# controller.net
KiCad netlist of a schematic drawn in EAGLE
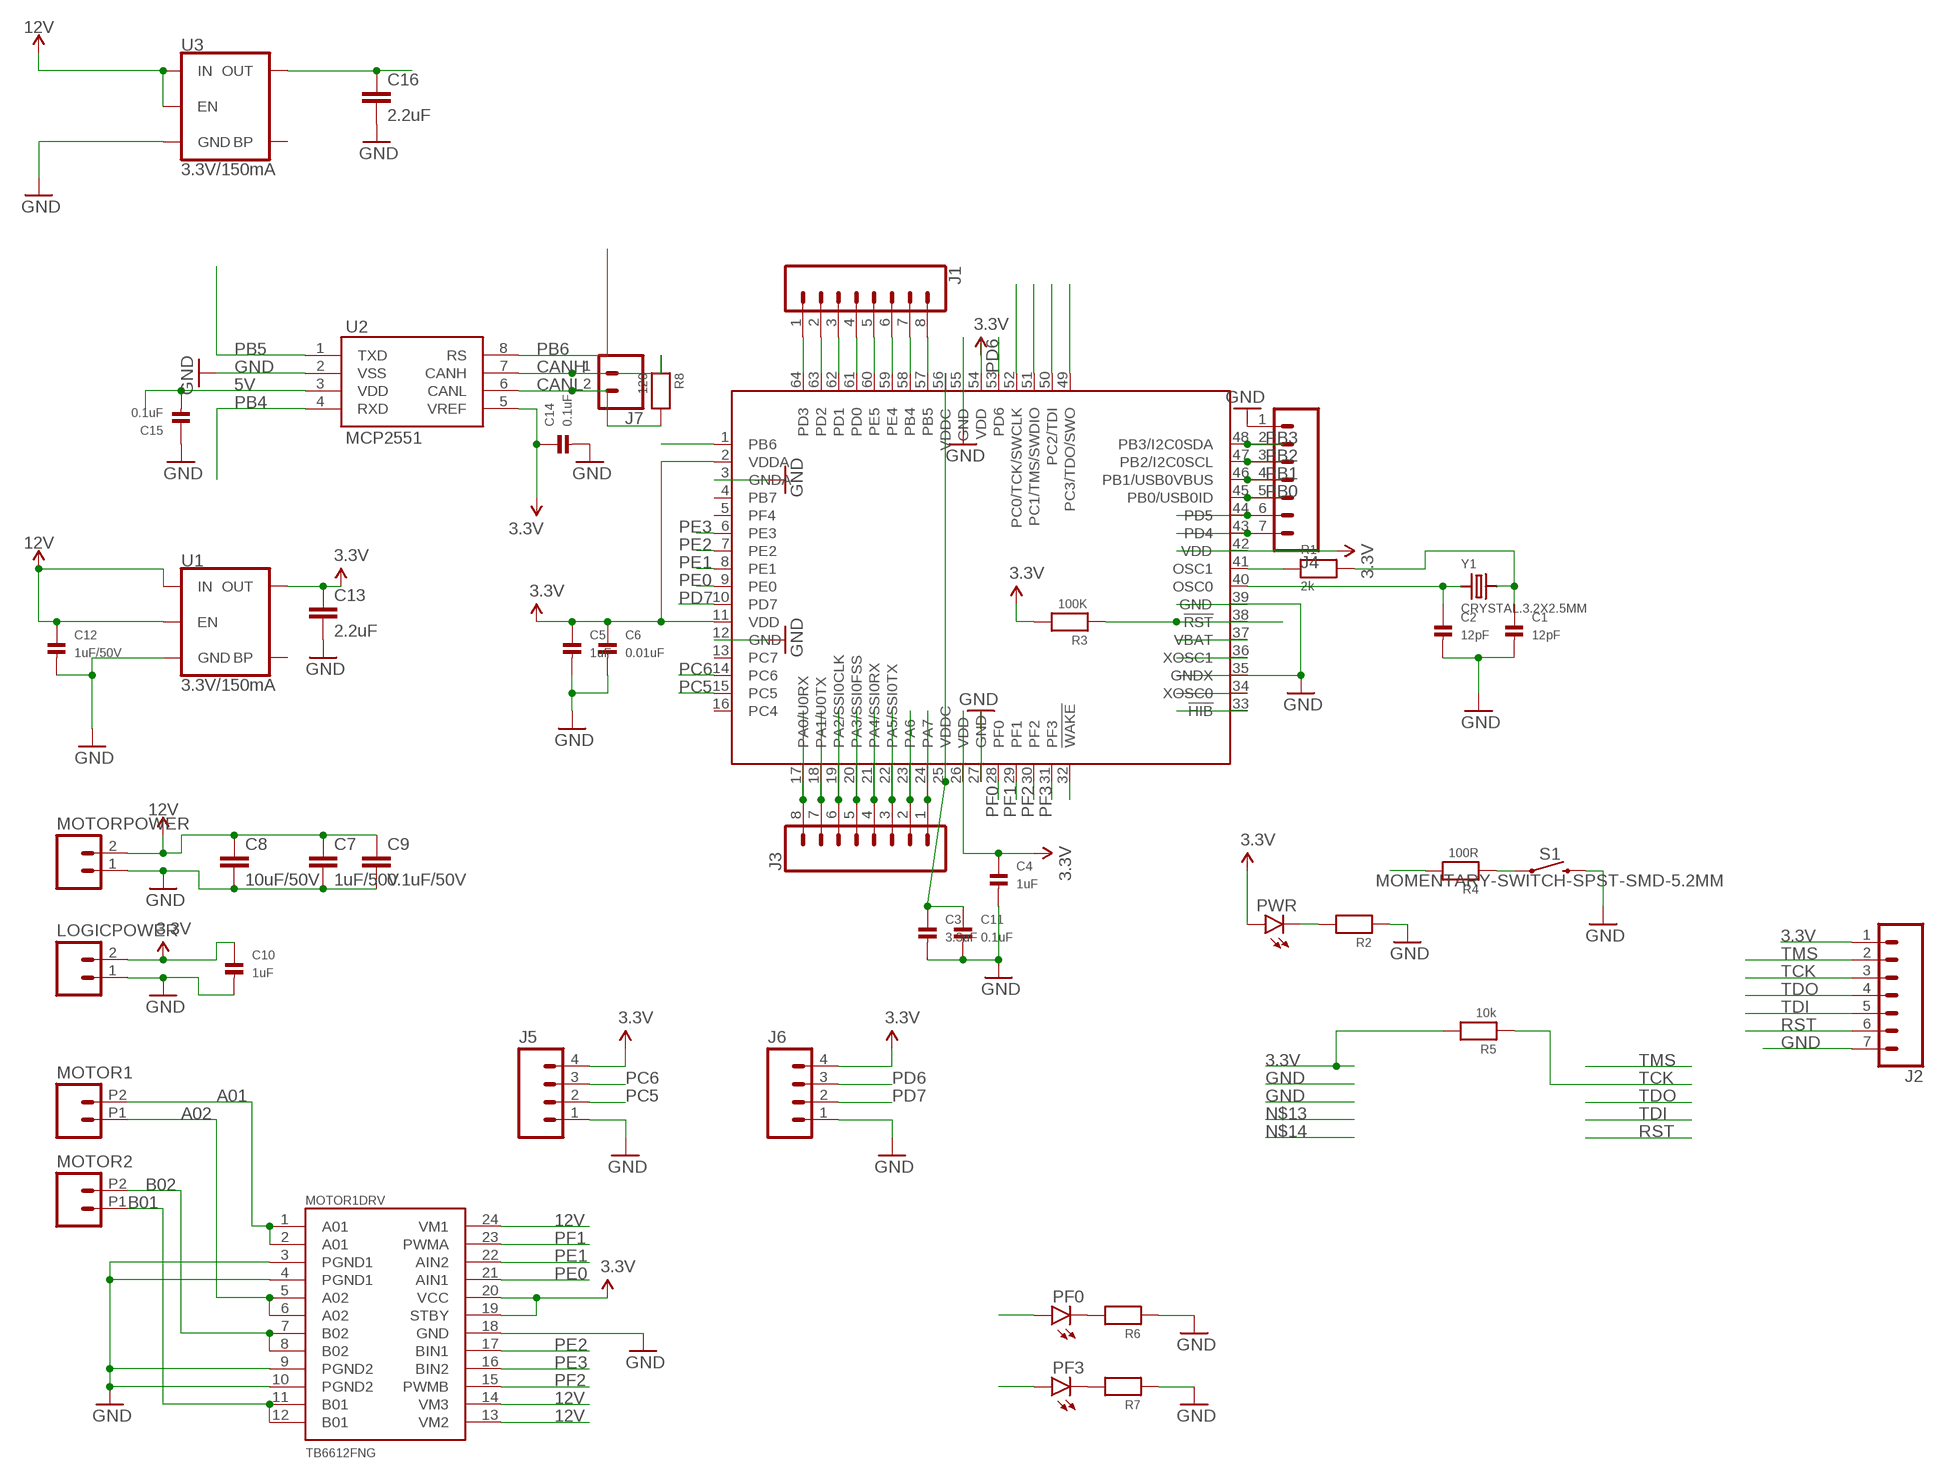
[diagram p0: schematic, sheet 1]

(export (version "E")
  (design (tool "Eeschema 10.0.6"))
  (components
    (comp (ref "C1")
      (value "12pF")
      (footprint "eagle-import:_0603MP")
      (libsource (lib "eagle-import") (part "CAP_CERAMIC_0603MP"))
    )
    (comp (ref "C2")
      (value "12pF")
      (footprint "eagle-import:_0603MP")
      (libsource (lib "eagle-import") (part "CAP_CERAMIC_0603MP"))
    )
    (comp (ref "C3")
      (value "3.3uF")
      (footprint "eagle-import:_0603MP")
      (libsource (lib "eagle-import") (part "CAP_CERAMIC_0603MP"))
    )
    (comp (ref "C4")
      (value "1uF")
      (footprint "eagle-import:_0603MP")
      (libsource (lib "eagle-import") (part "CAP_CERAMIC_0603MP"))
    )
    (comp (ref "C5")
      (value "1uF")
      (footprint "eagle-import:_0603MP")
      (libsource (lib "eagle-import") (part "CAP_CERAMIC_0603MP"))
    )
    (comp (ref "C6")
      (value "0.01uF")
      (footprint "eagle-import:_0603MP")
      (libsource (lib "eagle-import") (part "CAP_CERAMIC_0603MP"))
    )
    (comp (ref "C7")
      (value "1uF/50V")
      (footprint "eagle-import:0603-CAP")
      (libsource (lib "eagle-import") (part "0.1UF-25V(+80/-20%)(0603)"))
    )
    (comp (ref "C8")
      (value "10uF/50V")
      (footprint "eagle-import:0805-CAP")
      (libsource (lib "eagle-import") (part "1.0UF-25V-+80/-20(0805){dblquote}"))
    )
    (comp (ref "C9")
      (value "0.1uF/50V")
      (footprint "eagle-import:0603-CAP")
      (libsource (lib "eagle-import") (part "0.1UF-25V(+80/-20%)(0603)"))
    )
    (comp (ref "C10")
      (value "1uF")
      (footprint "eagle-import:_0603MP")
      (libsource (lib "eagle-import") (part "CAP_CERAMIC_0603MP"))
    )
    (comp (ref "C11")
      (value "0.1uF")
      (footprint "eagle-import:_0603MP")
      (libsource (lib "eagle-import") (part "CAP_CERAMIC_0603MP"))
    )
    (comp (ref "C12")
      (value "1uF/50V")
      (footprint "eagle-import:_0603MP")
      (libsource (lib "eagle-import") (part "CAP_CERAMIC_0603MP"))
    )
    (comp (ref "C13")
      (value "2.2uF")
      (footprint "eagle-import:0805")
      (libsource (lib "eagle-import") (part "2.2UF-0805-25V-(+80/-20%)"))
    )
    (comp (ref "C14")
      (value "0.1uF")
      (footprint "eagle-import:_0603MP")
      (libsource (lib "eagle-import") (part "CAP_CERAMIC_0603MP"))
    )
    (comp (ref "C15")
      (value "0.1uF")
      (footprint "eagle-import:_0603MP")
      (libsource (lib "eagle-import") (part "CAP_CERAMIC_0603MP"))
    )
    (comp (ref "C16")
      (value "2.2uF")
      (footprint "eagle-import:0805")
      (libsource (lib "eagle-import") (part "2.2UF-0805-25V-(+80/-20%)"))
    )
    (comp (ref "IC1")
      (value "TM4C123[7,G]XXPM")
      (footprint "eagle-import:PM_S-PQFP-G64")
      (libsource (lib "eagle-import") (part "TM4C123[7,G]XXPM"))
    )
    (comp (ref "J1")
      (value "CONN_08\"")
      (footprint "eagle-import:1X08@1")
      (libsource (lib "eagle-import") (part "CONN_08{dblquote}"))
    )
    (comp (ref "J2")
      (value "CONN_07")
      (footprint "eagle-import:1X07@1")
      (libsource (lib "eagle-import") (part "CONN_07"))
    )
    (comp (ref "J3")
      (value "CONN_08\"")
      (footprint "eagle-import:1X08@1")
      (libsource (lib "eagle-import") (part "CONN_08{dblquote}"))
    )
    (comp (ref "J4")
      (value "M07")
      (footprint "eagle-import:1X07")
      (libsource (lib "eagle-import") (part "M07"))
    )
    (comp (ref "J5")
      (value "M04PTH")
      (footprint "eagle-import:1X04")
      (libsource (lib "eagle-import") (part "M04PTH"))
    )
    (comp (ref "J6")
      (value "M04PTH")
      (footprint "eagle-import:1X04")
      (libsource (lib "eagle-import") (part "M04PTH"))
    )
    (comp (ref "J7")
      (value "CONN_02")
      (footprint "eagle-import:1X02")
      (libsource (lib "eagle-import") (part "CONN_02"))
    )
    (comp (ref "LOGICPOWER")
      (value "M02PTH")
      (footprint "eagle-import:1X02@1")
      (libsource (lib "eagle-import") (part "M02PTH"))
    )
    (comp (ref "MOTOR1")
      (value "M022.54MM_SCREWTERM")
      (footprint "eagle-import:1X02_2.54_SCREWTERM@1")
      (libsource (lib "eagle-import") (part "M022.54MM_SCREWTERM"))
    )
    (comp (ref "MOTOR1DRV")
      (value "TB6612FNG")
      (footprint "eagle-import:SSOP24")
      (libsource (lib "eagle-import") (part "TB6612FNG"))
    )
    (comp (ref "MOTOR2")
      (value "M022.54MM_SCREWTERM")
      (footprint "eagle-import:1X02_2.54_SCREWTERM@1")
      (libsource (lib "eagle-import") (part "M022.54MM_SCREWTERM"))
    )
    (comp (ref "MOTORPOWER")
      (value "M02PTH")
      (footprint "eagle-import:1X02@1")
      (libsource (lib "eagle-import") (part "M02PTH"))
    )
    (comp (ref "PF0")
      (value "LED0603")
      (footprint "eagle-import:LED-0603")
      (libsource (lib "eagle-import") (part "LED0603"))
    )
    (comp (ref "PF3")
      (value "LED0603")
      (footprint "eagle-import:LED-0603")
      (libsource (lib "eagle-import") (part "LED0603"))
    )
    (comp (ref "PWR")
      (value "LED0603")
      (footprint "eagle-import:LED-0603")
      (libsource (lib "eagle-import") (part "LED0603"))
    )
    (comp (ref "R1")
      (value "2k")
      (footprint "eagle-import:_0603MP")
      (libsource (lib "eagle-import") (part "RESISTOR_0603MP"))
    )
    (comp (ref "R2")
      (value "RESISTOR_0603MP")
      (footprint "eagle-import:_0603MP")
      (libsource (lib "eagle-import") (part "RESISTOR_0603MP"))
    )
    (comp (ref "R3")
      (value "100K")
      (footprint "eagle-import:_0603MP")
      (libsource (lib "eagle-import") (part "RESISTOR_0603MP"))
    )
    (comp (ref "R4")
      (value "100R")
      (footprint "eagle-import:_0603MP")
      (libsource (lib "eagle-import") (part "RESISTOR_0603MP"))
    )
    (comp (ref "R5")
      (value "10k")
      (footprint "eagle-import:_0603MP")
      (libsource (lib "eagle-import") (part "RESISTOR_0603MP"))
    )
    (comp (ref "R6")
      (value "RESISTOR_0603MP")
      (footprint "eagle-import:_0603MP")
      (libsource (lib "eagle-import") (part "RESISTOR_0603MP"))
    )
    (comp (ref "R7")
      (value "RESISTOR_0603MP")
      (footprint "eagle-import:_0603MP")
      (libsource (lib "eagle-import") (part "RESISTOR_0603MP"))
    )
    (comp (ref "R8")
      (value "120")
      (footprint "eagle-import:_0603MP")
      (libsource (lib "eagle-import") (part "RESISTOR_0603MP"))
    )
    (comp (ref "S1")
      (value "MOMENTARY-SWITCH-SPST-SMD-5.2MM")
      (footprint "eagle-import:TACTILE_SWITCH_SMD_5.2MM")
      (libsource (lib "eagle-import") (part "MOMENTARY-SWITCH-SPST-SMD-5.2MM"))
    )
    (comp (ref "U1")
      (value "3.3V/150mA")
      (footprint "eagle-import:SOT23-5")
      (libsource (lib "eagle-import") (part "V_REG_MIC52053.3V"))
    )
    (comp (ref "U2")
      (value "MCP2551")
      (footprint "eagle-import:SO08")
      (libsource (lib "eagle-import") (part "MCP2551"))
    )
    (comp (ref "U3")
      (value "3.3V/150mA")
      (footprint "eagle-import:SOT23-5")
      (libsource (lib "eagle-import") (part "V_REG_MIC52053.3V"))
    )
    (comp (ref "Y1")
      (value "CRYSTAL.3.2X2.5MM")
      (footprint "eagle-import:3.2X2.5MM")
      (libsource (lib "eagle-import") (part "CRYSTAL.3.2X2.5MM"))
    )
  )
  (nets
    (net (code "1") (name "/5V") (class "Default")
      (node (ref "C15") (pin "2") (pinfunction "P$2_2") (pintype "passive"))
      (node (ref "C16") (pin "1") (pinfunction "1_1") (pintype "passive"))
      (node (ref "U2") (pin "3") (pinfunction "VDD_3") (pintype "bidirectional"))
      (node (ref "U3") (pin "5") (pinfunction "OUT_5") (pintype "passive"))
    )
    (net (code "2") (name "/A01") (class "Default")
      (node (ref "MOTOR1") (pin "P2") (pinfunction "2_P2") (pintype "passive"))
      (node (ref "MOTOR1DRV") (pin "1") (pinfunction "A01_1") (pintype "bidirectional"))
      (node (ref "MOTOR1DRV") (pin "2") (pinfunction "A01_2") (pintype "bidirectional"))
    )
    (net (code "3") (name "/A02") (class "Default")
      (node (ref "MOTOR1") (pin "P1") (pinfunction "1_P1") (pintype "passive"))
      (node (ref "MOTOR1DRV") (pin "5") (pinfunction "A02_5") (pintype "bidirectional"))
      (node (ref "MOTOR1DRV") (pin "6") (pinfunction "A02_6") (pintype "bidirectional"))
    )
    (net (code "4") (name "/B01") (class "Default")
      (node (ref "MOTOR1DRV") (pin "11") (pinfunction "B01_11") (pintype "bidirectional"))
      (node (ref "MOTOR1DRV") (pin "12") (pinfunction "B01_12") (pintype "bidirectional"))
      (node (ref "MOTOR2") (pin "P1") (pinfunction "1_P1") (pintype "passive"))
    )
    (net (code "5") (name "/B02") (class "Default")
      (node (ref "MOTOR1DRV") (pin "7") (pinfunction "B02_7") (pintype "bidirectional"))
      (node (ref "MOTOR1DRV") (pin "8") (pinfunction "B02_8") (pintype "bidirectional"))
      (node (ref "MOTOR2") (pin "P2") (pinfunction "2_P2") (pintype "passive"))
    )
    (net (code "6") (name "/CANH") (class "Default")
      (node (ref "J7") (pin "1") (pinfunction "1_1") (pintype "passive"))
      (node (ref "R8") (pin "1") (pinfunction "1_1") (pintype "passive"))
      (node (ref "U2") (pin "7") (pinfunction "CANH_7") (pintype "bidirectional"))
    )
    (net (code "7") (name "/CANL") (class "Default")
      (node (ref "J7") (pin "2") (pinfunction "2_2") (pintype "passive"))
      (node (ref "R8") (pin "2") (pinfunction "2_2") (pintype "passive"))
      (node (ref "U2") (pin "6") (pinfunction "CANL_6") (pintype "bidirectional"))
    )
    (net (code "10") (name "/PB0") (class "Default")
      (node (ref "IC1") (pin "45") (pinfunction "PB0/USB0ID_45") (pintype "bidirectional"))
      (node (ref "J4") (pin "5") (pinfunction "5_5") (pintype "passive"))
    )
    (net (code "11") (name "/PB1") (class "Default")
      (node (ref "IC1") (pin "46") (pinfunction "PB1/USB0VBUS_46") (pintype "bidirectional"))
      (node (ref "J4") (pin "4") (pinfunction "4_4") (pintype "passive"))
    )
    (net (code "12") (name "/PB2") (class "Default")
      (node (ref "IC1") (pin "47") (pinfunction "PB2/I2C0SCL_47") (pintype "bidirectional"))
      (node (ref "J4") (pin "3") (pinfunction "3_3") (pintype "passive"))
    )
    (net (code "13") (name "/PB3") (class "Default")
      (node (ref "IC1") (pin "48") (pinfunction "PB3/I2C0SDA_48") (pintype "bidirectional"))
      (node (ref "J4") (pin "2") (pinfunction "2_2") (pintype "passive"))
    )
    (net (code "14") (name "/PB4") (class "Default")
      (node (ref "IC1") (pin "58") (pinfunction "PB4_58") (pintype "bidirectional"))
      (node (ref "J1") (pin "7") (pinfunction "7_7") (pintype "passive"))
      (node (ref "U2") (pin "4") (pinfunction "RXD_4") (pintype "bidirectional"))
    )
    (net (code "15") (name "/PB5") (class "Default")
      (node (ref "IC1") (pin "57") (pinfunction "PB5_57") (pintype "bidirectional"))
      (node (ref "J1") (pin "8") (pinfunction "8_8") (pintype "passive"))
      (node (ref "U2") (pin "1") (pinfunction "TXD_1") (pintype "bidirectional"))
    )
    (net (code "16") (name "/PB6") (class "Default")
      (node (ref "IC1") (pin "1") (pinfunction "PB6_1") (pintype "bidirectional"))
      (node (ref "U2") (pin "8") (pinfunction "RS_8") (pintype "bidirectional"))
    )
    (net (code "17") (name "/PC5") (class "Default")
      (node (ref "IC1") (pin "15") (pinfunction "PC5_15") (pintype "bidirectional"))
      (node (ref "J5") (pin "2") (pinfunction "2_2") (pintype "passive"))
    )
    (net (code "18") (name "/PC6") (class "Default")
      (node (ref "IC1") (pin "14") (pinfunction "PC6_14") (pintype "bidirectional"))
      (node (ref "J5") (pin "3") (pinfunction "3_3") (pintype "passive"))
    )
    (net (code "19") (name "/PD6") (class "Default")
      (node (ref "IC1") (pin "53") (pinfunction "PD6_53") (pintype "bidirectional"))
      (node (ref "J6") (pin "3") (pinfunction "3_3") (pintype "passive"))
    )
    (net (code "20") (name "/PD7") (class "Default")
      (node (ref "IC1") (pin "10") (pinfunction "PD7_10") (pintype "bidirectional"))
      (node (ref "J6") (pin "2") (pinfunction "2_2") (pintype "passive"))
    )
    (net (code "21") (name "/PE0") (class "Default")
      (node (ref "IC1") (pin "9") (pinfunction "PE0_9") (pintype "bidirectional"))
      (node (ref "MOTOR1DRV") (pin "21") (pinfunction "AIN1_21") (pintype "bidirectional"))
    )
    (net (code "22") (name "/PE1") (class "Default")
      (node (ref "IC1") (pin "8") (pinfunction "PE1_8") (pintype "bidirectional"))
      (node (ref "MOTOR1DRV") (pin "22") (pinfunction "AIN2_22") (pintype "bidirectional"))
    )
    (net (code "23") (name "/PE2") (class "Default")
      (node (ref "IC1") (pin "7") (pinfunction "PE2_7") (pintype "bidirectional"))
      (node (ref "MOTOR1DRV") (pin "17") (pinfunction "BIN1_17") (pintype "bidirectional"))
    )
    (net (code "24") (name "/PE3") (class "Default")
      (node (ref "IC1") (pin "6") (pinfunction "PE3_6") (pintype "bidirectional"))
      (node (ref "MOTOR1DRV") (pin "16") (pinfunction "BIN2_16") (pintype "bidirectional"))
    )
    (net (code "25") (name "/PF0") (class "Default")
      (node (ref "IC1") (pin "28") (pinfunction "PF0_28") (pintype "bidirectional"))
      (node (ref "PF0") (pin "A") (pinfunction "A_A") (pintype "passive"))
    )
    (net (code "26") (name "/PF1") (class "Default")
      (node (ref "IC1") (pin "29") (pinfunction "PF1_29") (pintype "bidirectional"))
      (node (ref "MOTOR1DRV") (pin "23") (pinfunction "PWMA_23") (pintype "bidirectional"))
    )
    (net (code "27") (name "/PF2") (class "Default")
      (node (ref "IC1") (pin "30") (pinfunction "PF2_30") (pintype "bidirectional"))
      (node (ref "MOTOR1DRV") (pin "15") (pinfunction "PWMB_15") (pintype "bidirectional"))
    )
    (net (code "28") (name "/PF3") (class "Default")
      (node (ref "IC1") (pin "31") (pinfunction "PF3_31") (pintype "bidirectional"))
      (node (ref "PF3") (pin "A") (pinfunction "A_A") (pintype "passive"))
    )
    (net (code "29") (name "/RST") (class "Default")
      (node (ref "IC1") (pin "38") (pinfunction "~{RST}_38") (pintype "bidirectional"))
      (node (ref "J2") (pin "6") (pinfunction "6_6") (pintype "passive"))
      (node (ref "R3") (pin "1") (pinfunction "1_1") (pintype "passive"))
      (node (ref "R4") (pin "2") (pinfunction "2_2") (pintype "passive"))
    )
    (net (code "30") (name "/TCK") (class "Default")
      (node (ref "IC1") (pin "52") (pinfunction "PC0/TCK/SWCLK_52") (pintype "bidirectional"))
      (node (ref "J2") (pin "3") (pinfunction "3_3") (pintype "passive"))
      (node (ref "R5") (pin "1") (pinfunction "1_1") (pintype "passive"))
    )
    (net (code "31") (name "/TDI") (class "Default")
      (node (ref "IC1") (pin "50") (pinfunction "PC2/TDI_50") (pintype "bidirectional"))
      (node (ref "J2") (pin "5") (pinfunction "5_5") (pintype "passive"))
    )
    (net (code "32") (name "/TDO") (class "Default")
      (node (ref "IC1") (pin "49") (pinfunction "PC3/TDO/SWO_49") (pintype "bidirectional"))
      (node (ref "J2") (pin "4") (pinfunction "4_4") (pintype "passive"))
    )
    (net (code "33") (name "/TMS") (class "Default")
      (node (ref "IC1") (pin "51") (pinfunction "PC1/TMS/SWDIO_51") (pintype "bidirectional"))
      (node (ref "J2") (pin "2") (pinfunction "2_2") (pintype "passive"))
    )
    (net (code "34") (name "3.3V") (class "Default")
      (node (ref "C10") (pin "1") (pinfunction "P$1_1") (pintype "passive"))
      (node (ref "C13") (pin "1") (pinfunction "1_1") (pintype "passive"))
      (node (ref "C14") (pin "1") (pinfunction "P$1_1") (pintype "passive"))
      (node (ref "C4") (pin "1") (pinfunction "P$1_1") (pintype "passive"))
      (node (ref "C5") (pin "1") (pinfunction "P$1_1") (pintype "passive"))
      (node (ref "C6") (pin "1") (pinfunction "P$1_1") (pintype "passive"))
      (node (ref "IC1") (pin "11") (pinfunction "VDD_11") (pintype "bidirectional"))
      (node (ref "IC1") (pin "2") (pinfunction "VDDA_2") (pintype "bidirectional"))
      (node (ref "IC1") (pin "26") (pinfunction "VDD_26") (pintype "bidirectional"))
      (node (ref "IC1") (pin "42") (pinfunction "VDD_42") (pintype "bidirectional"))
      (node (ref "IC1") (pin "54") (pinfunction "VDD_54") (pintype "bidirectional"))
      (node (ref "J2") (pin "1") (pinfunction "1_1") (pintype "passive"))
      (node (ref "J5") (pin "4") (pinfunction "4_4") (pintype "passive"))
      (node (ref "J6") (pin "4") (pinfunction "4_4") (pintype "passive"))
      (node (ref "LOGICPOWER") (pin "2") (pinfunction "2_2") (pintype "passive"))
      (node (ref "MOTOR1DRV") (pin "19") (pinfunction "STBY_19") (pintype "bidirectional"))
      (node (ref "MOTOR1DRV") (pin "20") (pinfunction "VCC_20") (pintype "bidirectional"))
      (node (ref "PWR") (pin "A") (pinfunction "A_A") (pintype "passive"))
      (node (ref "R3") (pin "2") (pinfunction "2_2") (pintype "passive"))
      (node (ref "R5") (pin "2") (pinfunction "2_2") (pintype "passive"))
      (node (ref "U1") (pin "5") (pinfunction "OUT_5") (pintype "passive"))
      (node (ref "U2") (pin "5") (pinfunction "VREF_5") (pintype "bidirectional"))
    )
    (net (code "35") (name "12V") (class "Default")
      (node (ref "C12") (pin "1") (pinfunction "P$1_1") (pintype "passive"))
      (node (ref "C7") (pin "1") (pinfunction "1_1") (pintype "passive"))
      (node (ref "C8") (pin "1") (pinfunction "1_1") (pintype "passive"))
      (node (ref "C9") (pin "1") (pinfunction "1_1") (pintype "passive"))
      (node (ref "MOTOR1DRV") (pin "13") (pinfunction "VM2_13") (pintype "bidirectional"))
      (node (ref "MOTOR1DRV") (pin "14") (pinfunction "VM3_14") (pintype "bidirectional"))
      (node (ref "MOTOR1DRV") (pin "24") (pinfunction "VM1_24") (pintype "bidirectional"))
      (node (ref "MOTORPOWER") (pin "2") (pinfunction "2_2") (pintype "passive"))
      (node (ref "U1") (pin "1") (pinfunction "IN_1") (pintype "input"))
      (node (ref "U1") (pin "3") (pinfunction "EN_3") (pintype "input"))
      (node (ref "U3") (pin "1") (pinfunction "IN_1") (pintype "input"))
      (node (ref "U3") (pin "3") (pinfunction "EN_3") (pintype "input"))
    )
    (net (code "36") (name "GND") (class "Default")
      (node (ref "C1") (pin "2") (pinfunction "P$2_2") (pintype "passive"))
      (node (ref "C10") (pin "2") (pinfunction "P$2_2") (pintype "passive"))
      (node (ref "C11") (pin "2") (pinfunction "P$2_2") (pintype "passive"))
      (node (ref "C12") (pin "2") (pinfunction "P$2_2") (pintype "passive"))
      (node (ref "C13") (pin "2") (pinfunction "2_2") (pintype "passive"))
      (node (ref "C14") (pin "2") (pinfunction "P$2_2") (pintype "passive"))
      (node (ref "C15") (pin "1") (pinfunction "P$1_1") (pintype "passive"))
      (node (ref "C16") (pin "2") (pinfunction "2_2") (pintype "passive"))
      (node (ref "C2") (pin "2") (pinfunction "P$2_2") (pintype "passive"))
      (node (ref "C3") (pin "2") (pinfunction "P$2_2") (pintype "passive"))
      (node (ref "C4") (pin "2") (pinfunction "P$2_2") (pintype "passive"))
      (node (ref "C5") (pin "2") (pinfunction "P$2_2") (pintype "passive"))
      (node (ref "C6") (pin "2") (pinfunction "P$2_2") (pintype "passive"))
      (node (ref "C7") (pin "2") (pinfunction "2_2") (pintype "passive"))
      (node (ref "C8") (pin "2") (pinfunction "2_2") (pintype "passive"))
      (node (ref "C9") (pin "2") (pinfunction "2_2") (pintype "passive"))
      (node (ref "IC1") (pin "12") (pinfunction "GND_12") (pintype "bidirectional"))
      (node (ref "IC1") (pin "27") (pinfunction "GND_27") (pintype "bidirectional"))
      (node (ref "IC1") (pin "3") (pinfunction "GNDA_3") (pintype "bidirectional"))
      (node (ref "IC1") (pin "35") (pinfunction "GNDX_35") (pintype "bidirectional"))
      (node (ref "IC1") (pin "39") (pinfunction "GND_39") (pintype "bidirectional"))
      (node (ref "IC1") (pin "55") (pinfunction "GND_55") (pintype "bidirectional"))
      (node (ref "J2") (pin "7") (pinfunction "7_7") (pintype "passive"))
      (node (ref "J4") (pin "1") (pinfunction "1_1") (pintype "passive"))
      (node (ref "J5") (pin "1") (pinfunction "1_1") (pintype "passive"))
      (node (ref "J6") (pin "1") (pinfunction "1_1") (pintype "passive"))
      (node (ref "LOGICPOWER") (pin "1") (pinfunction "1_1") (pintype "passive"))
      (node (ref "MOTOR1DRV") (pin "10") (pinfunction "PGND2_10") (pintype "bidirectional"))
      (node (ref "MOTOR1DRV") (pin "18") (pinfunction "GND_18") (pintype "bidirectional"))
      (node (ref "MOTOR1DRV") (pin "3") (pinfunction "PGND1_3") (pintype "bidirectional"))
      (node (ref "MOTOR1DRV") (pin "4") (pinfunction "PGND1_4") (pintype "bidirectional"))
      (node (ref "MOTOR1DRV") (pin "9") (pinfunction "PGND2_9") (pintype "bidirectional"))
      (node (ref "MOTORPOWER") (pin "1") (pinfunction "1_1") (pintype "passive"))
      (node (ref "R2") (pin "1") (pinfunction "1_1") (pintype "passive"))
      (node (ref "R6") (pin "1") (pinfunction "1_1") (pintype "passive"))
      (node (ref "R7") (pin "1") (pinfunction "1_1") (pintype "passive"))
      (node (ref "S1") (pin "3") (pinfunction "2_3") (pintype "passive"))
      (node (ref "U1") (pin "2") (pinfunction "GND_2") (pintype "input"))
      (node (ref "U2") (pin "2") (pinfunction "VSS_2") (pintype "bidirectional"))
      (node (ref "U3") (pin "2") (pinfunction "GND_2") (pintype "input"))
    )
    (net (code "37") (name "Net-(C1-P$1)") (class "Default")
      (node (ref "C1") (pin "1") (pinfunction "P$1_1") (pintype "passive"))
      (node (ref "R1") (pin "2") (pinfunction "2_2") (pintype "passive"))
      (node (ref "Y1") (pin "3") (pinfunction "2_3") (pintype "passive"))
    )
    (net (code "38") (name "Net-(C2-P$1)") (class "Default")
      (node (ref "C2") (pin "1") (pinfunction "P$1_1") (pintype "passive"))
      (node (ref "IC1") (pin "40") (pinfunction "OSC0_40") (pintype "bidirectional"))
      (node (ref "Y1") (pin "1") (pinfunction "1_1") (pintype "passive"))
    )
    (net (code "39") (name "Net-(C11-P$1)") (class "Default")
      (node (ref "C11") (pin "1") (pinfunction "P$1_1") (pintype "passive"))
      (node (ref "C3") (pin "1") (pinfunction "P$1_1") (pintype "passive"))
      (node (ref "IC1") (pin "25") (pinfunction "VDDC_25") (pintype "bidirectional"))
      (node (ref "IC1") (pin "56") (pinfunction "VDDC_56") (pintype "bidirectional"))
    )
    (net (code "40") (name "Net-(IC1-OSC1)") (class "Default")
      (node (ref "IC1") (pin "41") (pinfunction "OSC1_41") (pintype "bidirectional"))
      (node (ref "R1") (pin "1") (pinfunction "1_1") (pintype "passive"))
    )
    (net (code "41") (name "Net-(IC1-PA0{slash}U0RX)") (class "Default")
      (node (ref "IC1") (pin "17") (pinfunction "PA0/U0RX_17") (pintype "bidirectional"))
      (node (ref "J3") (pin "8") (pinfunction "8_8") (pintype "passive"))
    )
    (net (code "42") (name "Net-(IC1-PA1{slash}U0TX)") (class "Default")
      (node (ref "IC1") (pin "18") (pinfunction "PA1/U0TX_18") (pintype "bidirectional"))
      (node (ref "J3") (pin "7") (pinfunction "7_7") (pintype "passive"))
    )
    (net (code "43") (name "Net-(IC1-PA2{slash}SSI0CLK)") (class "Default")
      (node (ref "IC1") (pin "19") (pinfunction "PA2/SSI0CLK_19") (pintype "bidirectional"))
      (node (ref "J3") (pin "6") (pinfunction "6_6") (pintype "passive"))
    )
    (net (code "44") (name "Net-(IC1-PA3{slash}SSI0FSS)") (class "Default")
      (node (ref "IC1") (pin "20") (pinfunction "PA3/SSI0FSS_20") (pintype "bidirectional"))
      (node (ref "J3") (pin "5") (pinfunction "5_5") (pintype "passive"))
    )
    (net (code "45") (name "Net-(IC1-PA4{slash}SSI0RX)") (class "Default")
      (node (ref "IC1") (pin "21") (pinfunction "PA4/SSI0RX_21") (pintype "bidirectional"))
      (node (ref "J3") (pin "4") (pinfunction "4_4") (pintype "passive"))
    )
    (net (code "46") (name "Net-(IC1-PA5{slash}SSI0TX)") (class "Default")
      (node (ref "IC1") (pin "22") (pinfunction "PA5/SSI0TX_22") (pintype "bidirectional"))
      (node (ref "J3") (pin "3") (pinfunction "3_3") (pintype "passive"))
    )
    (net (code "47") (name "Net-(IC1-PA6)") (class "Default")
      (node (ref "IC1") (pin "23") (pinfunction "PA6_23") (pintype "bidirectional"))
      (node (ref "J3") (pin "2") (pinfunction "2_2") (pintype "passive"))
    )
    (net (code "48") (name "Net-(IC1-PA7)") (class "Default")
      (node (ref "IC1") (pin "24") (pinfunction "PA7_24") (pintype "bidirectional"))
      (node (ref "J3") (pin "1") (pinfunction "1_1") (pintype "passive"))
    )
    (net (code "49") (name "Net-(IC1-PD0)") (class "Default")
      (node (ref "IC1") (pin "61") (pinfunction "PD0_61") (pintype "bidirectional"))
      (node (ref "J1") (pin "4") (pinfunction "4_4") (pintype "passive"))
    )
    (net (code "50") (name "Net-(IC1-PD1)") (class "Default")
      (node (ref "IC1") (pin "62") (pinfunction "PD1_62") (pintype "bidirectional"))
      (node (ref "J1") (pin "3") (pinfunction "3_3") (pintype "passive"))
    )
    (net (code "51") (name "Net-(IC1-PD2)") (class "Default")
      (node (ref "IC1") (pin "63") (pinfunction "PD2_63") (pintype "bidirectional"))
      (node (ref "J1") (pin "2") (pinfunction "2_2") (pintype "passive"))
    )
    (net (code "52") (name "Net-(IC1-PD3)") (class "Default")
      (node (ref "IC1") (pin "64") (pinfunction "PD3_64") (pintype "bidirectional"))
      (node (ref "J1") (pin "1") (pinfunction "1_1") (pintype "passive"))
    )
    (net (code "53") (name "Net-(IC1-PD4)") (class "Default")
      (node (ref "IC1") (pin "43") (pinfunction "PD4_43") (pintype "bidirectional"))
      (node (ref "J4") (pin "7") (pinfunction "7_7") (pintype "passive"))
    )
    (net (code "54") (name "Net-(IC1-PD5)") (class "Default")
      (node (ref "IC1") (pin "44") (pinfunction "PD5_44") (pintype "bidirectional"))
      (node (ref "J4") (pin "6") (pinfunction "6_6") (pintype "passive"))
    )
    (net (code "55") (name "Net-(IC1-PE4)") (class "Default")
      (node (ref "IC1") (pin "59") (pinfunction "PE4_59") (pintype "bidirectional"))
      (node (ref "J1") (pin "6") (pinfunction "6_6") (pintype "passive"))
    )
    (net (code "56") (name "Net-(IC1-PE5)") (class "Default")
      (node (ref "IC1") (pin "60") (pinfunction "PE5_60") (pintype "bidirectional"))
      (node (ref "J1") (pin "5") (pinfunction "5_5") (pintype "passive"))
    )
    (net (code "57") (name "Net-(PF0-PadC)") (class "Default")
      (node (ref "PF0") (pin "C") (pinfunction "C_C") (pintype "passive"))
      (node (ref "R6") (pin "2") (pinfunction "2_2") (pintype "passive"))
    )
    (net (code "58") (name "Net-(PF3-PadC)") (class "Default")
      (node (ref "PF3") (pin "C") (pinfunction "C_C") (pintype "passive"))
      (node (ref "R7") (pin "2") (pinfunction "2_2") (pintype "passive"))
    )
    (net (code "59") (name "Net-(PWR-PadC)") (class "Default")
      (node (ref "PWR") (pin "C") (pinfunction "C_C") (pintype "passive"))
      (node (ref "R2") (pin "2") (pinfunction "2_2") (pintype "passive"))
    )
    (net (code "60") (name "Net-(R4-Pad1)") (class "Default")
      (node (ref "R4") (pin "1") (pinfunction "1_1") (pintype "passive"))
      (node (ref "S1") (pin "1") (pinfunction "1_1") (pintype "passive"))
    )
    (net (code "61") (name "unconnected-(IC1-PB7-Pad4)") (class "Default")
      (node (ref "IC1") (pin "4") (pinfunction "PB7_4") (pintype "bidirectional"))
    )
    (net (code "62") (name "unconnected-(IC1-PC4-Pad16)") (class "Default")
      (node (ref "IC1") (pin "16") (pinfunction "PC4_16") (pintype "bidirectional"))
    )
    (net (code "63") (name "unconnected-(IC1-PC7-Pad13)") (class "Default")
      (node (ref "IC1") (pin "13") (pinfunction "PC7_13") (pintype "bidirectional"))
    )
    (net (code "64") (name "unconnected-(IC1-PF4-Pad5)") (class "Default")
      (node (ref "IC1") (pin "5") (pinfunction "PF4_5") (pintype "bidirectional"))
    )
    (net (code "65") (name "unconnected-(IC1-VBAT-Pad37)") (class "Default")
      (node (ref "IC1") (pin "37") (pinfunction "VBAT_37") (pintype "bidirectional"))
    )
    (net (code "66") (name "unconnected-(IC1-XOSC0-Pad34)") (class "Default")
      (node (ref "IC1") (pin "34") (pinfunction "XOSC0_34") (pintype "bidirectional"))
    )
    (net (code "67") (name "unconnected-(IC1-XOSC1-Pad36)") (class "Default")
      (node (ref "IC1") (pin "36") (pinfunction "XOSC1_36") (pintype "bidirectional"))
    )
    (net (code "68") (name "unconnected-(IC1-~{HIB}-Pad33)") (class "Default")
      (node (ref "IC1") (pin "33") (pinfunction "~{HIB}_33") (pintype "bidirectional"))
    )
    (net (code "69") (name "unconnected-(IC1-~{WAKE}-Pad32)") (class "Default")
      (node (ref "IC1") (pin "32") (pinfunction "~{WAKE}_32") (pintype "bidirectional"))
    )
    (net (code "70") (name "unconnected-(U1-BP-Pad4)") (class "Default")
      (node (ref "U1") (pin "4") (pinfunction "BP_4") (pintype "input"))
    )
    (net (code "71") (name "unconnected-(U3-BP-Pad4)") (class "Default")
      (node (ref "U3") (pin "4") (pinfunction "BP_4") (pintype "input"))
    )
  )
)
